# COM_Board.net
KiCad netlist of a schematic drawn in EAGLE
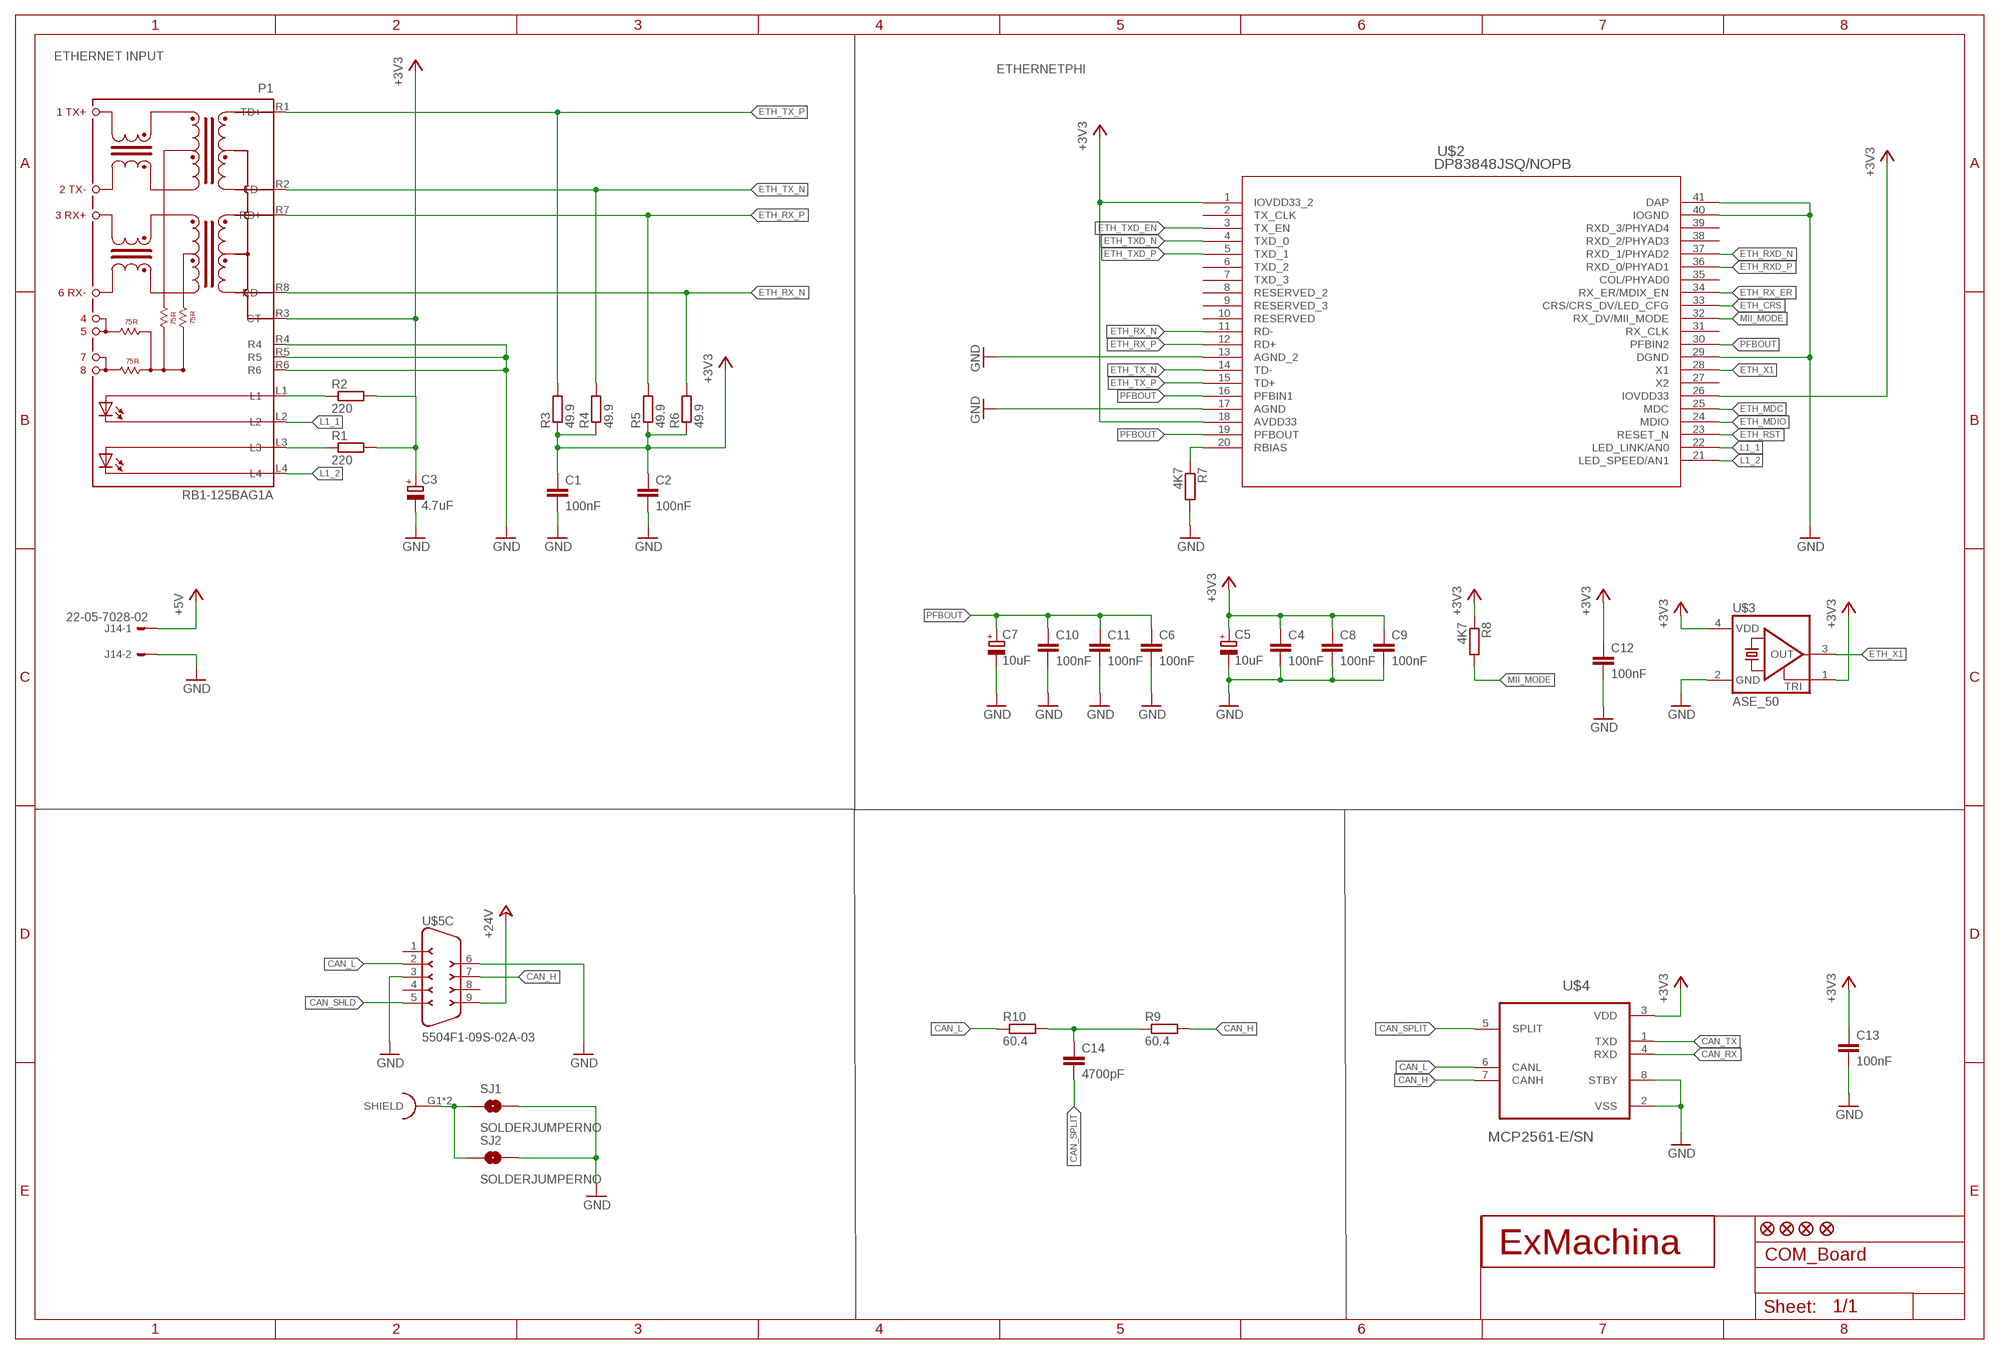
[diagram p0: schematic, sheet 1]

(export (version "E")
  (design (tool "Eeschema 10.0.6"))
  (components
    (comp (ref "C1")
      (value "100nF")
      (footprint "eagle-import:C0603")
      (libsource (lib "eagle-import") (part "C-EUC0603"))
    )
    (comp (ref "C2")
      (value "100nF")
      (footprint "eagle-import:C0603")
      (libsource (lib "eagle-import") (part "C-EUC0603"))
    )
    (comp (ref "C3")
      (value "4.7uF")
      (footprint "eagle-import:CT3216")
      (libsource (lib "eagle-import") (part "CPOL-EUCT3216"))
    )
    (comp (ref "C4")
      (value "100nF")
      (footprint "eagle-import:C0603")
      (libsource (lib "eagle-import") (part "C-EUC0603"))
    )
    (comp (ref "C5")
      (value "10uF")
      (footprint "eagle-import:CT3216")
      (libsource (lib "eagle-import") (part "CPOL-EUCT3216"))
    )
    (comp (ref "C6")
      (value "100nF")
      (footprint "eagle-import:C0603")
      (libsource (lib "eagle-import") (part "C-EUC0603"))
    )
    (comp (ref "C7")
      (value "10uF")
      (footprint "eagle-import:CT3216")
      (libsource (lib "eagle-import") (part "CPOL-EUCT3216"))
    )
    (comp (ref "C8")
      (value "100nF")
      (footprint "eagle-import:C0603")
      (libsource (lib "eagle-import") (part "C-EUC0603"))
    )
    (comp (ref "C9")
      (value "100nF")
      (footprint "eagle-import:C0603")
      (libsource (lib "eagle-import") (part "C-EUC0603"))
    )
    (comp (ref "C10")
      (value "100nF")
      (footprint "eagle-import:C0603")
      (libsource (lib "eagle-import") (part "C-EUC0603"))
    )
    (comp (ref "C11")
      (value "100nF")
      (footprint "eagle-import:C0603")
      (libsource (lib "eagle-import") (part "C-EUC0603"))
    )
    (comp (ref "C12")
      (value "100nF")
      (footprint "eagle-import:C0603")
      (libsource (lib "eagle-import") (part "C-EUC0603"))
    )
    (comp (ref "C13")
      (value "100nF")
      (footprint "eagle-import:C0603")
      (libsource (lib "eagle-import") (part "C-EUC0603"))
    )
    (comp (ref "C14")
      (value "4700pF")
      (footprint "eagle-import:C0603")
      (libsource (lib "eagle-import") (part "C-EUC0603"))
    )
    (comp (ref "J14")
      (value "22-05-7028-02")
      (footprint "eagle-import:7395-02")
      (libsource (lib "eagle-import") (part "22-?-0205-7028"))
    )
    (comp (ref "JP2")
      (value "FIDUCIAL1X2")
      (footprint "eagle-import:FIDUCIAL-1X2")
      (libsource (lib "eagle-import") (part "FIDUCIAL1X2"))
    )
    (comp (ref "JP3")
      (value "FIDUCIAL1X2")
      (footprint "eagle-import:FIDUCIAL-1X2")
      (libsource (lib "eagle-import") (part "FIDUCIAL1X2"))
    )
    (comp (ref "JP4")
      (value "FIDUCIAL1X2")
      (footprint "eagle-import:FIDUCIAL-1X2")
      (libsource (lib "eagle-import") (part "FIDUCIAL1X2"))
    )
    (comp (ref "JP5")
      (value "FIDUCIAL1X2")
      (footprint "eagle-import:FIDUCIAL-1X2")
      (libsource (lib "eagle-import") (part "FIDUCIAL1X2"))
    )
    (comp (ref "P1")
      (value "RB1-125BAG1A")
      (footprint "eagle-import:WIZNET_RB1-125BAG1A")
      (libsource (lib "eagle-import") (part "RB1-125BAG1A"))
    )
    (comp (ref "R1")
      (value "220")
      (footprint "eagle-import:R0603")
      (libsource (lib "eagle-import") (part "R-EU_R0603"))
    )
    (comp (ref "R2")
      (value "220")
      (footprint "eagle-import:R0603")
      (libsource (lib "eagle-import") (part "R-EU_R0603"))
    )
    (comp (ref "R3")
      (value "49.9")
      (footprint "eagle-import:R0603")
      (libsource (lib "eagle-import") (part "R-EU_R0603"))
    )
    (comp (ref "R4")
      (value "49.9")
      (footprint "eagle-import:R0603")
      (libsource (lib "eagle-import") (part "R-EU_R0603"))
    )
    (comp (ref "R5")
      (value "49.9")
      (footprint "eagle-import:R0603")
      (libsource (lib "eagle-import") (part "R-EU_R0603"))
    )
    (comp (ref "R6")
      (value "49.9")
      (footprint "eagle-import:R0603")
      (libsource (lib "eagle-import") (part "R-EU_R0603"))
    )
    (comp (ref "R7")
      (value "4K7")
      (footprint "eagle-import:R0603")
      (libsource (lib "eagle-import") (part "R-EU_R0603"))
    )
    (comp (ref "R8")
      (value "4K7")
      (footprint "eagle-import:R0603")
      (libsource (lib "eagle-import") (part "R-EU_R0603"))
    )
    (comp (ref "R9")
      (value "60.4")
      (footprint "eagle-import:R0603")
      (libsource (lib "eagle-import") (part "R-EU_R0603"))
    )
    (comp (ref "R10")
      (value "60.4")
      (footprint "eagle-import:R0603")
      (libsource (lib "eagle-import") (part "R-EU_R0603"))
    )
    (comp (ref "SJ1")
      (value "SOLDERJUMPERNO")
      (footprint "eagle-import:SJ_2S-NO")
      (libsource (lib "eagle-import") (part "SOLDERJUMPERNO"))
    )
    (comp (ref "SJ2")
      (value "SOLDERJUMPERNO")
      (footprint "eagle-import:SJ_2S-NO")
      (libsource (lib "eagle-import") (part "SOLDERJUMPERNO"))
    )
    (comp (ref "U$1")
      (value "EXMACHINA-LOGO-NAME")
      (footprint "eagle-import:EXM-LOGO-BASELINE")
      (libsource (lib "eagle-import") (part "EXMACHINA-LOGO-NAME"))
    )
    (comp (ref "U$2")
      (value "DP83848JSQ/NOPB")
      (footprint "eagle-import:SQA40B")
      (fields
        (field (name "MANUFACTURER_PART_NUMBER") "dp83848jsqnopb")
        (field (name "COPYRIGHT") "Copyright (C) 2015 Accelerated Designs. All rights reserved")
      )
      (libsource (lib "eagle-import") (part "DP83848JSQ/NOPB"))
    )
    (comp (ref "U$3")
      (value "ASE_50")
      (footprint "eagle-import:ASE")
      (libsource (lib "eagle-import") (part "ASE"))
    )
    (comp (ref "U$4")
      (value "MCP2561-E/SN")
      (footprint "eagle-import:SOIC127P600X175-8N")
      (fields (field (name "MPN") "MCP2551-I/SN"))
      (libsource (lib "eagle-import") (part "MCP2561-E/SN"))
    )
    (comp (ref "U$5")
      (value "5504F1-09S-02A-03")
      (footprint "eagle-import:5504F1-09S-02A")
      (libsource (lib "eagle-import") (part "5504F1-09S-02A-03"))
    )
  )
  (nets
    (net (code "1") (name "+3V3") (class "Default")
      (node (ref "C1") (pin "1") (pinfunction "1_1") (pintype "passive"))
      (node (ref "C12") (pin "1") (pinfunction "1_1") (pintype "passive"))
      (node (ref "C13") (pin "1") (pinfunction "1_1") (pintype "passive"))
      (node (ref "C2") (pin "1") (pinfunction "1_1") (pintype "passive"))
      (node (ref "C3") (pin "+") (pinfunction "+_+") (pintype "passive"))
      (node (ref "C4") (pin "1") (pinfunction "1_1") (pintype "passive"))
      (node (ref "C5") (pin "+") (pinfunction "+_+") (pintype "passive"))
      (node (ref "C8") (pin "1") (pinfunction "1_1") (pintype "passive"))
      (node (ref "C9") (pin "1") (pinfunction "1_1") (pintype "passive"))
      (node (ref "P1") (pin "R3") (pinfunction "CT_R3") (pintype "input"))
      (node (ref "R1") (pin "2") (pinfunction "2_2") (pintype "passive"))
      (node (ref "R2") (pin "2") (pinfunction "2_2") (pintype "passive"))
      (node (ref "R3") (pin "1") (pinfunction "1_1") (pintype "passive"))
      (node (ref "R4") (pin "1") (pinfunction "1_1") (pintype "passive"))
      (node (ref "R5") (pin "1") (pinfunction "1_1") (pintype "passive"))
      (node (ref "R6") (pin "1") (pinfunction "1_1") (pintype "passive"))
      (node (ref "R8") (pin "1") (pinfunction "1_1") (pintype "passive"))
      (node (ref "U$2") (pin "1") (pinfunction "IOVDD33_2_1") (pintype "power_in"))
      (node (ref "U$2") (pin "18") (pinfunction "AVDD33_18") (pintype "power_in"))
      (node (ref "U$2") (pin "26") (pinfunction "IOVDD33_26") (pintype "power_in"))
      (node (ref "U$3") (pin "1") (pinfunction "TRI_1") (pintype "input"))
      (node (ref "U$3") (pin "4") (pinfunction "VDD_4") (pintype "power_in"))
      (node (ref "U$4") (pin "3") (pinfunction "VDD_3") (pintype "power_in"))
    )
    (net (code "2") (name "+5V") (class "Default")
      (node (ref "J14") (pin "1") (pinfunction "S_1") (pintype "passive"))
    )
    (net (code "3") (name "+24V") (class "Default")
      (node (ref "U$5") (pin "9") (pinfunction "9_9") (pintype "passive"))
    )
    (net (code "4") (name "CAN_H") (class "Default")
      (node (ref "R9") (pin "2") (pinfunction "2_2") (pintype "passive"))
      (node (ref "U$4") (pin "7") (pinfunction "CANH_7") (pintype "bidirectional"))
      (node (ref "U$5") (pin "7") (pinfunction "7_7") (pintype "passive"))
    )
    (net (code "5") (name "CAN_L") (class "Default")
      (node (ref "R10") (pin "1") (pinfunction "1_1") (pintype "passive"))
      (node (ref "U$4") (pin "6") (pinfunction "CANL_6") (pintype "bidirectional"))
      (node (ref "U$5") (pin "2") (pinfunction "2_2") (pintype "passive"))
    )
    (net (code "6") (name "CAN_RX") (class "Default")
      (node (ref "U$4") (pin "4") (pinfunction "RXD_4") (pintype "output"))
    )
    (net (code "7") (name "CAN_SHLD") (class "Default")
      (node (ref "U$5") (pin "5") (pinfunction "5_5") (pintype "passive"))
    )
    (net (code "8") (name "CAN_SPLIT") (class "Default")
      (node (ref "C14") (pin "2") (pinfunction "2_2") (pintype "passive"))
      (node (ref "U$4") (pin "5") (pinfunction "SPLIT_5") (pintype "output"))
    )
    (net (code "9") (name "CAN_TX") (class "Default")
      (node (ref "U$4") (pin "1") (pinfunction "TXD_1") (pintype "input"))
    )
    (net (code "10") (name "ETH_CRS") (class "Default")
      (node (ref "U$2") (pin "33") (pinfunction "CRS/CRS_DV/LED_CFG_33") (pintype "output"))
    )
    (net (code "11") (name "ETH_MDC") (class "Default")
      (node (ref "U$2") (pin "25") (pinfunction "MDC_25") (pintype "input"))
    )
    (net (code "12") (name "ETH_MDIO") (class "Default")
      (node (ref "U$2") (pin "24") (pinfunction "MDIO_24") (pintype "bidirectional"))
    )
    (net (code "13") (name "ETH_RST") (class "Default")
      (node (ref "U$2") (pin "23") (pinfunction "RESET_N_23") (pintype "input"))
    )
    (net (code "14") (name "ETH_RXD_N") (class "Default")
      (node (ref "U$2") (pin "37") (pinfunction "RXD_1/PHYAD2_37") (pintype "output"))
    )
    (net (code "15") (name "ETH_RXD_P") (class "Default")
      (node (ref "U$2") (pin "36") (pinfunction "RXD_0/PHYAD1_36") (pintype "output"))
    )
    (net (code "16") (name "ETH_RX_ER") (class "Default")
      (node (ref "U$2") (pin "34") (pinfunction "RX_ER/MDIX_EN_34") (pintype "output"))
    )
    (net (code "17") (name "ETH_RX_N") (class "Default")
      (node (ref "P1") (pin "R8") (pinfunction "RD-_R8") (pintype "input"))
      (node (ref "R6") (pin "2") (pinfunction "2_2") (pintype "passive"))
      (node (ref "U$2") (pin "11") (pinfunction "RD-_11") (pintype "bidirectional"))
    )
    (net (code "18") (name "ETH_RX_P") (class "Default")
      (node (ref "P1") (pin "R7") (pinfunction "RD+_R7") (pintype "input"))
      (node (ref "R5") (pin "2") (pinfunction "2_2") (pintype "passive"))
      (node (ref "U$2") (pin "12") (pinfunction "RD+_12") (pintype "bidirectional"))
    )
    (net (code "19") (name "ETH_TXD_EN") (class "Default")
      (node (ref "U$2") (pin "3") (pinfunction "TX_EN_3") (pintype "input"))
    )
    (net (code "20") (name "ETH_TXD_N") (class "Default")
      (node (ref "U$2") (pin "4") (pinfunction "TXD_0_4") (pintype "input"))
    )
    (net (code "21") (name "ETH_TXD_P") (class "Default")
      (node (ref "U$2") (pin "5") (pinfunction "TXD_1_5") (pintype "input"))
    )
    (net (code "22") (name "ETH_TX_N") (class "Default")
      (node (ref "P1") (pin "R2") (pinfunction "TD-_R2") (pintype "input"))
      (node (ref "R4") (pin "2") (pinfunction "2_2") (pintype "passive"))
      (node (ref "U$2") (pin "14") (pinfunction "TD-_14") (pintype "bidirectional"))
    )
    (net (code "23") (name "ETH_TX_P") (class "Default")
      (node (ref "P1") (pin "R1") (pinfunction "TD+_R1") (pintype "input"))
      (node (ref "R3") (pin "2") (pinfunction "2_2") (pintype "passive"))
      (node (ref "U$2") (pin "15") (pinfunction "TD+_15") (pintype "bidirectional"))
    )
    (net (code "24") (name "ETH_X1") (class "Default")
      (node (ref "U$2") (pin "28") (pinfunction "X1_28") (pintype "input"))
      (node (ref "U$3") (pin "3") (pinfunction "OUT_3") (pintype "output"))
    )
    (net (code "25") (name "GND") (class "Default")
      (node (ref "C1") (pin "2") (pinfunction "2_2") (pintype "passive"))
      (node (ref "C10") (pin "2") (pinfunction "2_2") (pintype "passive"))
      (node (ref "C11") (pin "2") (pinfunction "2_2") (pintype "passive"))
      (node (ref "C12") (pin "2") (pinfunction "2_2") (pintype "passive"))
      (node (ref "C13") (pin "2") (pinfunction "2_2") (pintype "passive"))
      (node (ref "C2") (pin "2") (pinfunction "2_2") (pintype "passive"))
      (node (ref "C3") (pin "-") (pinfunction "-_-") (pintype "passive"))
      (node (ref "C4") (pin "2") (pinfunction "2_2") (pintype "passive"))
      (node (ref "C5") (pin "-") (pinfunction "-_-") (pintype "passive"))
      (node (ref "C6") (pin "2") (pinfunction "2_2") (pintype "passive"))
      (node (ref "C7") (pin "-") (pinfunction "-_-") (pintype "passive"))
      (node (ref "C8") (pin "2") (pinfunction "2_2") (pintype "passive"))
      (node (ref "C9") (pin "2") (pinfunction "2_2") (pintype "passive"))
      (node (ref "J14") (pin "2") (pinfunction "S_2") (pintype "passive"))
      (node (ref "P1") (pin "R4") (pinfunction "R4_R4") (pintype "input"))
      (node (ref "P1") (pin "R5") (pinfunction "R5_R5") (pintype "input"))
      (node (ref "P1") (pin "R6") (pinfunction "R6_R6") (pintype "input"))
      (node (ref "R7") (pin "2") (pinfunction "2_2") (pintype "passive"))
      (node (ref "SJ1") (pin "2") (pinfunction "2_2") (pintype "passive"))
      (node (ref "SJ2") (pin "2") (pinfunction "2_2") (pintype "passive"))
      (node (ref "U$2") (pin "13") (pinfunction "AGND_2_13") (pintype "power_in"))
      (node (ref "U$2") (pin "17") (pinfunction "AGND_17") (pintype "power_in"))
      (node (ref "U$2") (pin "29") (pinfunction "DGND_29") (pintype "power_in"))
      (node (ref "U$2") (pin "40") (pinfunction "IOGND_40") (pintype "power_in"))
      (node (ref "U$2") (pin "41") (pinfunction "DAP_41") (pintype "passive"))
      (node (ref "U$3") (pin "2") (pinfunction "GND_2") (pintype "power_in"))
      (node (ref "U$4") (pin "2") (pinfunction "VSS_2") (pintype "passive"))
      (node (ref "U$4") (pin "8") (pinfunction "STBY_8") (pintype "input"))
      (node (ref "U$5") (pin "3") (pinfunction "3_3") (pintype "passive"))
      (node (ref "U$5") (pin "6") (pinfunction "6_6") (pintype "passive"))
    )
    (net (code "26") (name "L1_1") (class "Default")
      (node (ref "P1") (pin "L2") (pinfunction "L2_L2") (pintype "passive"))
      (node (ref "U$2") (pin "22") (pinfunction "LED_LINK/AN0_22") (pintype "output"))
    )
    (net (code "27") (name "L1_2") (class "Default")
      (node (ref "P1") (pin "L4") (pinfunction "L4_L4") (pintype "passive"))
      (node (ref "U$2") (pin "21") (pinfunction "LED_SPEED/AN1_21") (pintype "output"))
    )
    (net (code "28") (name "MII_MODE") (class "Default")
      (node (ref "R8") (pin "2") (pinfunction "2_2") (pintype "passive"))
      (node (ref "U$2") (pin "32") (pinfunction "RX_DV/MII_MODE_32") (pintype "output"))
    )
    (net (code "29") (name "Net-(C14-Pad1)") (class "Default")
      (node (ref "C14") (pin "1") (pinfunction "1_1") (pintype "passive"))
      (node (ref "R10") (pin "2") (pinfunction "2_2") (pintype "passive"))
      (node (ref "R9") (pin "1") (pinfunction "1_1") (pintype "passive"))
    )
    (net (code "30") (name "Net-(P1-PadL1)") (class "Default")
      (node (ref "P1") (pin "L1") (pinfunction "L1_L1") (pintype "passive"))
      (node (ref "R2") (pin "1") (pinfunction "1_1") (pintype "passive"))
    )
    (net (code "31") (name "Net-(P1-PadL3)") (class "Default")
      (node (ref "P1") (pin "L3") (pinfunction "L3_L3") (pintype "passive"))
      (node (ref "R1") (pin "1") (pinfunction "1_1") (pintype "passive"))
    )
    (net (code "32") (name "Net-(SJ1-Pad1)") (class "Default")
      (node (ref "SJ1") (pin "1") (pinfunction "1_1") (pintype "passive"))
      (node (ref "SJ2") (pin "1") (pinfunction "1_1") (pintype "passive"))
      (node (ref "U$5") (pin "G1") (pinfunction "SHIELD_G1") (pintype "bidirectional"))
      (node (ref "U$5") (pin "G2") (pinfunction "SHIELD_G2") (pintype "bidirectional"))
    )
    (net (code "33") (name "Net-(U$2-RBIAS)") (class "Default")
      (node (ref "R7") (pin "1") (pinfunction "1_1") (pintype "passive"))
      (node (ref "U$2") (pin "20") (pinfunction "RBIAS_20") (pintype "input"))
    )
    (net (code "34") (name "PFBOUT") (class "Default")
      (node (ref "C10") (pin "1") (pinfunction "1_1") (pintype "passive"))
      (node (ref "C11") (pin "1") (pinfunction "1_1") (pintype "passive"))
      (node (ref "C6") (pin "1") (pinfunction "1_1") (pintype "passive"))
      (node (ref "C7") (pin "+") (pinfunction "+_+") (pintype "passive"))
      (node (ref "U$2") (pin "16") (pinfunction "PFBIN1_16") (pintype "input"))
      (node (ref "U$2") (pin "19") (pinfunction "PFBOUT_19") (pintype "output"))
      (node (ref "U$2") (pin "30") (pinfunction "PFBIN2_30") (pintype "input"))
    )
    (net (code "35") (name "unconnected-(U$2-COL{slash}PHYAD0-Pad35)") (class "Default")
      (node (ref "U$2") (pin "35") (pinfunction "COL/PHYAD0_35") (pintype "output"))
    )
    (net (code "36") (name "unconnected-(U$2-RESERVED-Pad10)") (class "Default")
      (node (ref "U$2") (pin "10") (pinfunction "RESERVED_10") (pintype "bidirectional"))
    )
    (net (code "37") (name "unconnected-(U$2-RESERVED_2-Pad8)") (class "Default")
      (node (ref "U$2") (pin "8") (pinfunction "RESERVED_2_8") (pintype "bidirectional"))
    )
    (net (code "38") (name "unconnected-(U$2-RESERVED_3-Pad9)") (class "Default")
      (node (ref "U$2") (pin "9") (pinfunction "RESERVED_3_9") (pintype "bidirectional"))
    )
    (net (code "39") (name "unconnected-(U$2-RXD_2{slash}PHYAD3-Pad38)") (class "Default")
      (node (ref "U$2") (pin "38") (pinfunction "RXD_2/PHYAD3_38") (pintype "output"))
    )
    (net (code "40") (name "unconnected-(U$2-RXD_3{slash}PHYAD4-Pad39)") (class "Default")
      (node (ref "U$2") (pin "39") (pinfunction "RXD_3/PHYAD4_39") (pintype "output"))
    )
    (net (code "41") (name "unconnected-(U$2-RX_CLK-Pad31)") (class "Default")
      (node (ref "U$2") (pin "31") (pinfunction "RX_CLK_31") (pintype "output"))
    )
    (net (code "42") (name "unconnected-(U$2-TXD_2-Pad6)") (class "Default")
      (node (ref "U$2") (pin "6") (pinfunction "TXD_2_6") (pintype "input"))
    )
    (net (code "43") (name "unconnected-(U$2-TXD_3-Pad7)") (class "Default")
      (node (ref "U$2") (pin "7") (pinfunction "TXD_3_7") (pintype "input"))
    )
    (net (code "44") (name "unconnected-(U$2-TX_CLK-Pad2)") (class "Default")
      (node (ref "U$2") (pin "2") (pinfunction "TX_CLK_2") (pintype "output"))
    )
    (net (code "45") (name "unconnected-(U$2-X2-Pad27)") (class "Default")
      (node (ref "U$2") (pin "27") (pinfunction "X2_27") (pintype "output"))
    )
    (net (code "46") (name "unconnected-(U$5-Pad1)") (class "Default")
      (node (ref "U$5") (pin "1") (pinfunction "1_1") (pintype "passive"))
    )
    (net (code "47") (name "unconnected-(U$5-Pad4)") (class "Default")
      (node (ref "U$5") (pin "4") (pinfunction "4_4") (pintype "passive"))
    )
    (net (code "48") (name "unconnected-(U$5-Pad8)") (class "Default")
      (node (ref "U$5") (pin "8") (pinfunction "8_8") (pintype "passive"))
    )
  )
)
